# power_supply_for_AOM.net
KiCad netlist of a schematic drawn in EAGLE
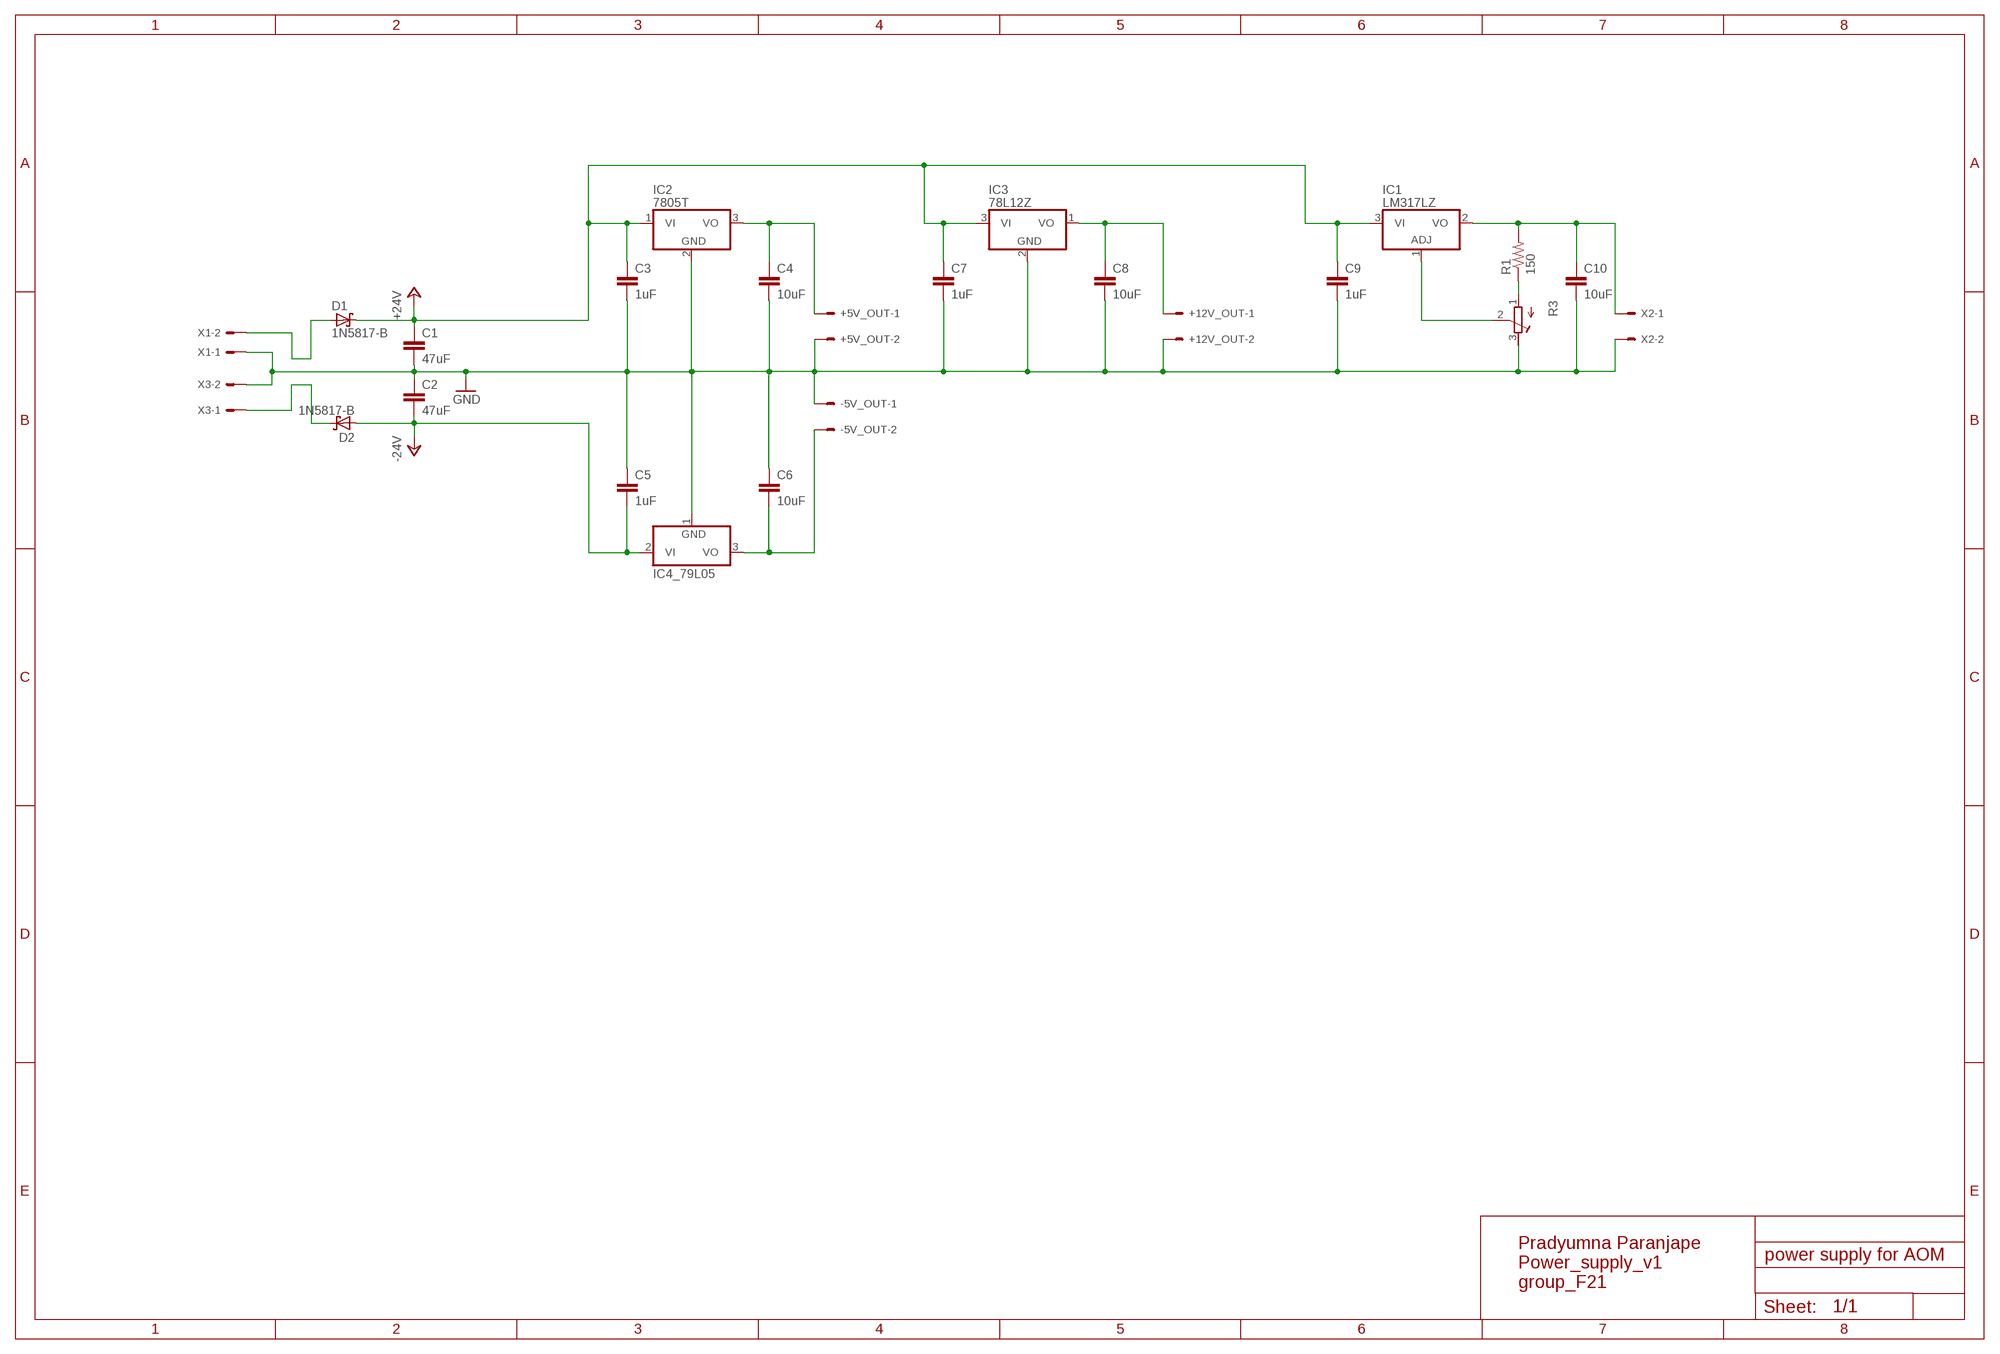
[diagram p0: schematic, sheet 1]

(export (version "E")
  (design (tool "Eeschema 10.0.6"))
  (components
    (comp (ref "+5V_OUT")
      (value "KK-156-2")
      (footprint "eagle-import:KK-156-2")
      (libsource (lib "eagle-import") (part "KK-156-2"))
    )
    (comp (ref "+12V_OUT")
      (value "KK-156-2")
      (footprint "eagle-import:KK-156-2")
      (libsource (lib "eagle-import") (part "KK-156-2"))
    )
    (comp (ref "-5V_OUT")
      (value "KK-156-2")
      (footprint "eagle-import:KK-156-2")
      (libsource (lib "eagle-import") (part "KK-156-2"))
    )
    (comp (ref "C1")
      (value "47uF")
      (footprint "eagle-import:C050-025X075")
      (libsource (lib "eagle-import") (part "C-EU050-025X075"))
    )
    (comp (ref "C2")
      (value "47uF")
      (footprint "eagle-import:C050-025X075")
      (libsource (lib "eagle-import") (part "C-EU050-025X075"))
    )
    (comp (ref "C3")
      (value "1uF")
      (footprint "eagle-import:C050-025X075")
      (libsource (lib "eagle-import") (part "C-EU050-025X075"))
    )
    (comp (ref "C4")
      (value "10uF")
      (footprint "eagle-import:C050-025X075")
      (libsource (lib "eagle-import") (part "C-EU050-025X075"))
    )
    (comp (ref "C5")
      (value "1uF")
      (footprint "eagle-import:C050-025X075")
      (libsource (lib "eagle-import") (part "C-EU050-025X075"))
    )
    (comp (ref "C6")
      (value "10uF")
      (footprint "eagle-import:C050-025X075")
      (libsource (lib "eagle-import") (part "C-EU050-025X075"))
    )
    (comp (ref "C7")
      (value "1uF")
      (footprint "eagle-import:C050-025X075")
      (libsource (lib "eagle-import") (part "C-EU050-025X075"))
    )
    (comp (ref "C8")
      (value "10uF")
      (footprint "eagle-import:C050-025X075")
      (libsource (lib "eagle-import") (part "C-EU050-025X075"))
    )
    (comp (ref "C9")
      (value "1uF")
      (footprint "eagle-import:C050-025X075")
      (libsource (lib "eagle-import") (part "C-EU050-025X075"))
    )
    (comp (ref "C10")
      (value "10uF")
      (footprint "eagle-import:C050-025X075")
      (libsource (lib "eagle-import") (part "C-EU050-025X075"))
    )
    (comp (ref "D1")
      (value "1N5817-B")
      (footprint "eagle-import:DO41-7.6")
      (libsource (lib "eagle-import") (part "1N5817-B"))
    )
    (comp (ref "D2")
      (value "1N5817-B")
      (footprint "eagle-import:DO41-7.6")
      (libsource (lib "eagle-import") (part "1N5817-B"))
    )
    (comp (ref "IC1")
      (value "LM317LZ")
      (footprint "eagle-import:TO92")
      (libsource (lib "eagle-import") (part "317LZLM"))
    )
    (comp (ref "IC2")
      (value "7805T")
      (footprint "eagle-import:TO220H")
      (libsource (lib "eagle-import") (part "78T05"))
    )
    (comp (ref "IC3")
      (value "78L12Z")
      (footprint "eagle-import:TO92")
      (libsource (lib "eagle-import") (part "78ZL12"))
    )
    (comp (ref "IC4_79L05")
      (value "7905L")
      (footprint "eagle-import:TO92")
      (libsource (lib "eagle-import") (part "79L05"))
    )
    (comp (ref "R1")
      (value "150")
      (footprint "eagle-import:0207_10")
      (libsource (lib "eagle-import") (part "R-US_0207/10"))
    )
    (comp (ref "R3")
      (value "R-TRIMM3296Y")
      (footprint "eagle-import:RTRIM3296Y")
      (libsource (lib "eagle-import") (part "R-TRIMM3296Y"))
    )
    (comp (ref "X1")
      (value "KK-156-2")
      (footprint "eagle-import:KK-156-2")
      (libsource (lib "eagle-import") (part "KK-156-2"))
    )
    (comp (ref "X2")
      (value "KK-156-2")
      (footprint "eagle-import:KK-156-2")
      (libsource (lib "eagle-import") (part "KK-156-2"))
    )
    (comp (ref "X3")
      (value "KK-156-2")
      (footprint "eagle-import:KK-156-2")
      (libsource (lib "eagle-import") (part "KK-156-2"))
    )
  )
  (nets
    (net (code "1") (name "+24V") (class "Default")
      (node (ref "C1") (pin "1") (pinfunction "1_1") (pintype "passive"))
      (node (ref "C3") (pin "1") (pinfunction "1_1") (pintype "passive"))
      (node (ref "C7") (pin "1") (pinfunction "1_1") (pintype "passive"))
      (node (ref "C9") (pin "1") (pinfunction "1_1") (pintype "passive"))
      (node (ref "D1") (pin "C") (pinfunction "C_C") (pintype "passive"))
      (node (ref "IC1") (pin "3") (pinfunction "VI_3") (pintype "input"))
      (node (ref "IC2") (pin "1") (pinfunction "VI_1") (pintype "input"))
      (node (ref "IC3") (pin "3") (pinfunction "VI_3") (pintype "input"))
    )
    (net (code "2") (name "-24V") (class "Default")
      (node (ref "C2") (pin "2") (pinfunction "2_2") (pintype "passive"))
      (node (ref "C5") (pin "2") (pinfunction "2_2") (pintype "passive"))
      (node (ref "D2") (pin "A") (pinfunction "A_A") (pintype "passive"))
      (node (ref "IC4_79L05") (pin "2") (pinfunction "VI_2") (pintype "input"))
    )
    (net (code "3") (name "GND") (class "Default")
      (node (ref "+12V_OUT") (pin "2") (pinfunction "S_2") (pintype "passive"))
      (node (ref "+5V_OUT") (pin "2") (pinfunction "S_2") (pintype "passive"))
      (node (ref "-5V_OUT") (pin "1") (pinfunction "S_1") (pintype "passive"))
      (node (ref "C1") (pin "2") (pinfunction "2_2") (pintype "passive"))
      (node (ref "C10") (pin "2") (pinfunction "2_2") (pintype "passive"))
      (node (ref "C2") (pin "1") (pinfunction "1_1") (pintype "passive"))
      (node (ref "C3") (pin "2") (pinfunction "2_2") (pintype "passive"))
      (node (ref "C4") (pin "2") (pinfunction "2_2") (pintype "passive"))
      (node (ref "C5") (pin "1") (pinfunction "1_1") (pintype "passive"))
      (node (ref "C6") (pin "1") (pinfunction "1_1") (pintype "passive"))
      (node (ref "C7") (pin "2") (pinfunction "2_2") (pintype "passive"))
      (node (ref "C8") (pin "2") (pinfunction "2_2") (pintype "passive"))
      (node (ref "C9") (pin "2") (pinfunction "2_2") (pintype "passive"))
      (node (ref "IC2") (pin "2") (pinfunction "GND_2") (pintype "passive"))
      (node (ref "IC3") (pin "2") (pinfunction "GND_2") (pintype "passive"))
      (node (ref "IC4_79L05") (pin "1") (pinfunction "GND_1") (pintype "passive"))
      (node (ref "R3") (pin "3") (pinfunction "E_3") (pintype "passive"))
      (node (ref "X1") (pin "1") (pinfunction "S_1") (pintype "passive"))
      (node (ref "X2") (pin "2") (pinfunction "S_2") (pintype "passive"))
      (node (ref "X3") (pin "2") (pinfunction "S_2") (pintype "passive"))
    )
    (net (code "4") (name "Net-(+5V_OUTA-S)") (class "Default")
      (node (ref "+5V_OUT") (pin "1") (pinfunction "S_1") (pintype "passive"))
      (node (ref "C4") (pin "1") (pinfunction "1_1") (pintype "passive"))
      (node (ref "IC2") (pin "3") (pinfunction "VO_3") (pintype "passive"))
    )
    (net (code "5") (name "Net-(+12V_OUTA-S)") (class "Default")
      (node (ref "+12V_OUT") (pin "1") (pinfunction "S_1") (pintype "passive"))
      (node (ref "C8") (pin "1") (pinfunction "1_1") (pintype "passive"))
      (node (ref "IC3") (pin "1") (pinfunction "VO_1") (pintype "passive"))
    )
    (net (code "6") (name "Net-(-5V_OUTB-S)") (class "Default")
      (node (ref "-5V_OUT") (pin "2") (pinfunction "S_2") (pintype "passive"))
      (node (ref "C6") (pin "2") (pinfunction "2_2") (pintype "passive"))
      (node (ref "IC4_79L05") (pin "3") (pinfunction "VO_3") (pintype "passive"))
    )
    (net (code "7") (name "Net-(IC1-ADJ)") (class "Default")
      (node (ref "IC1") (pin "1") (pinfunction "ADJ_1") (pintype "input"))
      (node (ref "R3") (pin "2") (pinfunction "S_2") (pintype "passive"))
    )
    (net (code "8") (name "Net-(IC1-VO)") (class "Default")
      (node (ref "C10") (pin "1") (pinfunction "1_1") (pintype "passive"))
      (node (ref "IC1") (pin "2") (pinfunction "VO_2") (pintype "passive"))
      (node (ref "R1") (pin "2") (pinfunction "2_2") (pintype "passive"))
      (node (ref "X2") (pin "1") (pinfunction "S_1") (pintype "passive"))
    )
    (net (code "9") (name "Net-(R3-A)") (class "Default")
      (node (ref "R1") (pin "1") (pinfunction "1_1") (pintype "passive"))
      (node (ref "R3") (pin "1") (pinfunction "A_1") (pintype "passive"))
    )
    (net (code "10") (name "Net-(X1B-S)") (class "Default")
      (node (ref "D1") (pin "A") (pinfunction "A_A") (pintype "passive"))
      (node (ref "X1") (pin "2") (pinfunction "S_2") (pintype "passive"))
    )
    (net (code "11") (name "Net-(X3A-S)") (class "Default")
      (node (ref "D2") (pin "C") (pinfunction "C_C") (pintype "passive"))
      (node (ref "X3") (pin "1") (pinfunction "S_1") (pintype "passive"))
    )
  )
)
